# flexNT2_V1_0.net
KiCad netlist of a schematic drawn in EAGLE
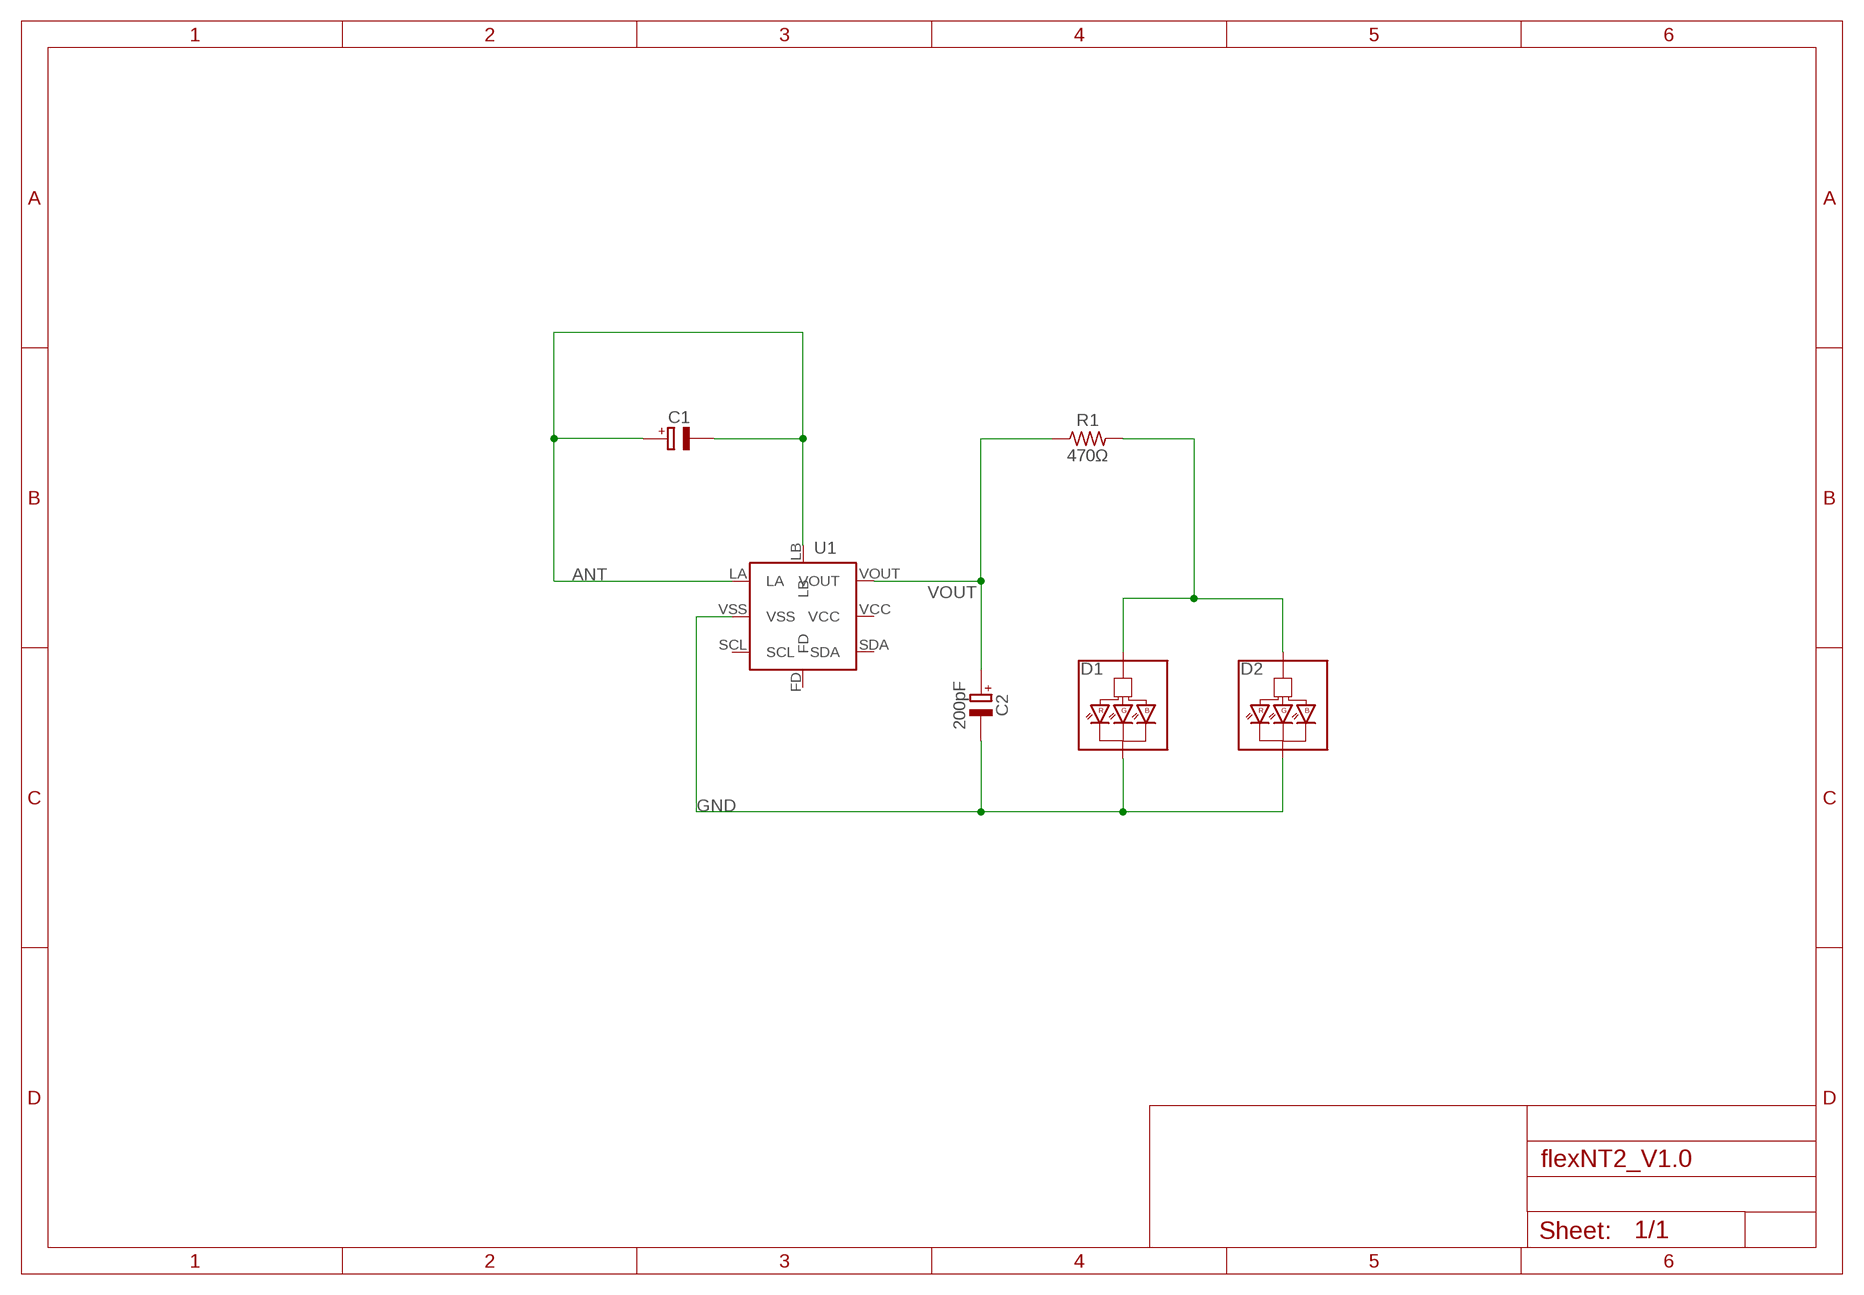
[diagram p0: schematic, sheet 1]

(export (version "E")
  (design (tool "Eeschema 10.0.6"))
  (components
    (comp (ref "C1")
      (value "C_POL_0603_FLEX")
      (footprint "eagle-import:0603_FLEX_C_POL")
      (libsource (lib "eagle-import") (part "C_POL_0603_FLEX"))
    )
    (comp (ref "C2")
      (value "200pF")
      (footprint "eagle-import:0603_FLEX_C_POL")
      (libsource (lib "eagle-import") (part "C_POL_0603_FLEX"))
    )
    (comp (ref "D1")
      (value "CZINELIGHT_0807RGBFF")
      (footprint "eagle-import:0807RGBFF_CZINELIGHT")
      (libsource (lib "eagle-import") (part "CZINELIGHT_0807RGBFF"))
    )
    (comp (ref "D2")
      (value "CZINELIGHT_0807RGBFF")
      (footprint "eagle-import:0807RGBFF_CZINELIGHT")
      (libsource (lib "eagle-import") (part "CZINELIGHT_0807RGBFF"))
    )
    (comp (ref "R1")
      (value "470Ω")
      (footprint "eagle-import:0603_FLEX")
      (libsource (lib "eagle-import") (part "R_0603_FLEX"))
    )
    (comp (ref "U1")
      (value "NTAG-I2C+")
      (footprint "eagle-import:XQFN8_NTAG-I2C+")
      (libsource (lib "eagle-import") (part "NTAG-I2C+"))
    )
  )
  (nets
    (net (code "1") (name "/ANT") (class "Default")
      (node (ref "C1") (pin "P$1") (pinfunction "+_P$1") (pintype "passive"))
      (node (ref "C1") (pin "P$2") (pinfunction "-_P$2") (pintype "passive"))
      (node (ref "U1") (pin "LA") (pinfunction "LA_LA") (pintype "bidirectional"))
      (node (ref "U1") (pin "LB") (pinfunction "LB_LB") (pintype "bidirectional"))
    )
    (net (code "2") (name "/GND") (class "Default")
      (node (ref "C2") (pin "P$2") (pinfunction "-_P$2") (pintype "passive"))
      (node (ref "D1") (pin "P$2") (pinfunction "C_P$2") (pintype "passive"))
      (node (ref "D2") (pin "P$2") (pinfunction "C_P$2") (pintype "passive"))
      (node (ref "U1") (pin "VSS") (pinfunction "VSS_VSS") (pintype "bidirectional"))
    )
    (net (code "3") (name "/VOUT") (class "Default")
      (node (ref "C2") (pin "P$1") (pinfunction "+_P$1") (pintype "passive"))
      (node (ref "R1") (pin "P$1") (pinfunction "1_P$1") (pintype "passive"))
      (node (ref "U1") (pin "VOUT") (pinfunction "VOUT_VOUT") (pintype "bidirectional"))
    )
    (net (code "4") (name "Net-(D1-A)") (class "Default")
      (node (ref "D1") (pin "P$1") (pinfunction "A_P$1") (pintype "passive"))
      (node (ref "D2") (pin "P$1") (pinfunction "A_P$1") (pintype "passive"))
      (node (ref "R1") (pin "P$2") (pinfunction "2_P$2") (pintype "passive"))
    )
    (net (code "5") (name "unconnected-(U1-PadFD)") (class "Default")
      (node (ref "U1") (pin "FD") (pinfunction "FD_FD") (pintype "bidirectional"))
    )
    (net (code "6") (name "unconnected-(U1-PadSCL)") (class "Default")
      (node (ref "U1") (pin "SCL") (pinfunction "SCL_SCL") (pintype "bidirectional"))
    )
    (net (code "7") (name "unconnected-(U1-PadSDA)") (class "Default")
      (node (ref "U1") (pin "SDA") (pinfunction "SDA_SDA") (pintype "bidirectional"))
    )
    (net (code "8") (name "unconnected-(U1-PadVCC)") (class "Default")
      (node (ref "U1") (pin "VCC") (pinfunction "VCC_VCC") (pintype "bidirectional"))
    )
  )
)
